# Digital.net
KiCad netlist of a schematic drawn in Altium Designer
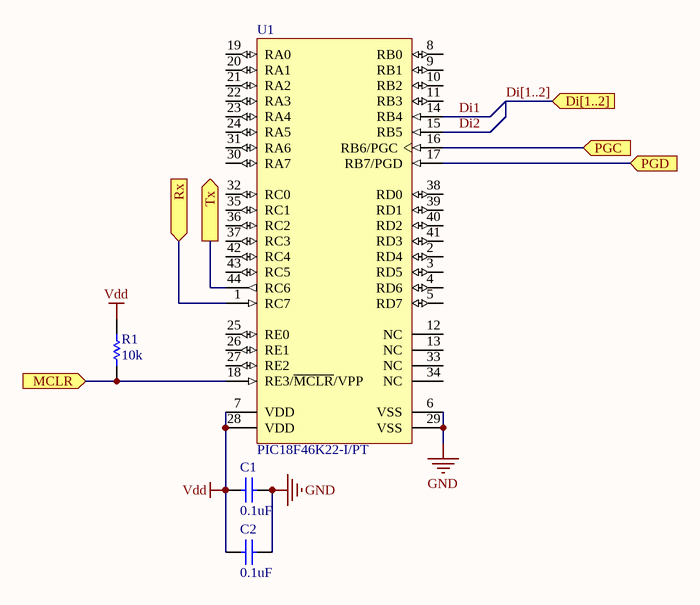
[diagram p0: Digital.SchDoc]

(export (version "E")
  (design (tool "Eeschema 10.0.6"))
  (components
    (comp (ref "C1")
      (value "0.1uF")
      (footprint "1608[0603]")
      (description "Capacitor")
      (fields (field (name "Comment") "Cap") (field (name "PUBLISHER") "Altium Limited"))
      (libsource (lib "Miscellaneous Devices") (part "Cap"))
    )
    (comp (ref "C2")
      (value "0.1uF")
      (footprint "1608[0603]")
      (description "Capacitor")
      (fields (field (name "Comment") "Cap") (field (name "PUBLISHER") "Altium Limited"))
      (libsource (lib "Miscellaneous Devices") (part "Cap"))
    )
    (comp (ref "R1")
      (value "10k")
      (footprint "C1206")
      (description "Resistor")
      (fields (field (name "Comment") "Res1") (field (name "PUBLISHER") "Altium Limited"))
      (libsource (lib "Miscellaneous Devices") (part "Res1"))
    )
    (comp (ref "U1")
      (value "PIC18F46K22-I/PT")
      (footprint "MCHP-TQFP-PT44_N")
      (fields (field (name "MANUFACTURER") "Microchip"))
      (libsource (lib "Microchip PIC18") (part "PIC18F46K22-I/PT"))
    )
  )
  (nets
    (net (code "1") (name "/Di1") (class "Default")
      (node (ref "U1") (pin "14") (pinfunction "RB4_14") (pintype "input"))
    )
    (net (code "2") (name "/Di2") (class "Default")
      (node (ref "U1") (pin "15") (pinfunction "RB5_15") (pintype "input"))
    )
    (net (code "4") (name "/MCLR") (class "Default")
      (node (ref "R1") (pin "2") (pinfunction "2_2") (pintype "passive"))
      (node (ref "U1") (pin "18") (pinfunction "RE3/~{MCLR}/VPP_18") (pintype "input"))
    )
    (net (code "5") (name "/PGC") (class "Default")
      (node (ref "U1") (pin "16") (pinfunction "RB6/PGC_16") (pintype "input"))
    )
    (net (code "6") (name "/PGD") (class "Default")
      (node (ref "U1") (pin "17") (pinfunction "RB7/PGD_17") (pintype "input"))
    )
    (net (code "7") (name "/Rx") (class "Default")
      (node (ref "U1") (pin "1") (pinfunction "RC7_1") (pintype "input"))
    )
    (net (code "8") (name "/Tx") (class "Default")
      (node (ref "U1") (pin "44") (pinfunction "RC6_44") (pintype "output"))
    )
    (net (code "9") (name "GND") (class "Default")
      (node (ref "C1") (pin "1") (pinfunction "1_1") (pintype "passive"))
      (node (ref "C2") (pin "1") (pinfunction "1_1") (pintype "passive"))
      (node (ref "U1") (pin "29") (pinfunction "VSS_29") (pintype "power_in"))
      (node (ref "U1") (pin "6") (pinfunction "VSS_6") (pintype "power_in"))
    )
    (net (code "10") (name "Vdd") (class "Default")
      (node (ref "C1") (pin "2") (pinfunction "2_2") (pintype "passive"))
      (node (ref "C2") (pin "2") (pinfunction "2_2") (pintype "passive"))
      (node (ref "R1") (pin "1") (pinfunction "1_1") (pintype "passive"))
      (node (ref "U1") (pin "28") (pinfunction "VDD_28") (pintype "power_in"))
      (node (ref "U1") (pin "7") (pinfunction "VDD_7") (pintype "power_in"))
    )
    (net (code "11") (name "unconnected-(U1-NC-Pad12)") (class "Default")
      (node (ref "U1") (pin "12") (pinfunction "NC_12") (pintype "passive"))
    )
    (net (code "12") (name "unconnected-(U1-NC-Pad13)") (class "Default")
      (node (ref "U1") (pin "13") (pinfunction "NC_13") (pintype "passive"))
    )
    (net (code "13") (name "unconnected-(U1-NC-Pad33)") (class "Default")
      (node (ref "U1") (pin "33") (pinfunction "NC_33") (pintype "passive"))
    )
    (net (code "14") (name "unconnected-(U1-NC-Pad34)") (class "Default")
      (node (ref "U1") (pin "34") (pinfunction "NC_34") (pintype "passive"))
    )
    (net (code "15") (name "unconnected-(U1-RA0-Pad19)") (class "Default")
      (node (ref "U1") (pin "19") (pinfunction "RA0_19") (pintype "bidirectional"))
    )
    (net (code "16") (name "unconnected-(U1-RA1-Pad20)") (class "Default")
      (node (ref "U1") (pin "20") (pinfunction "RA1_20") (pintype "bidirectional"))
    )
    (net (code "17") (name "unconnected-(U1-RA2-Pad21)") (class "Default")
      (node (ref "U1") (pin "21") (pinfunction "RA2_21") (pintype "bidirectional"))
    )
    (net (code "18") (name "unconnected-(U1-RA3-Pad22)") (class "Default")
      (node (ref "U1") (pin "22") (pinfunction "RA3_22") (pintype "bidirectional"))
    )
    (net (code "19") (name "unconnected-(U1-RA4-Pad23)") (class "Default")
      (node (ref "U1") (pin "23") (pinfunction "RA4_23") (pintype "bidirectional"))
    )
    (net (code "20") (name "unconnected-(U1-RA5-Pad24)") (class "Default")
      (node (ref "U1") (pin "24") (pinfunction "RA5_24") (pintype "bidirectional"))
    )
    (net (code "21") (name "unconnected-(U1-RA6-Pad31)") (class "Default")
      (node (ref "U1") (pin "31") (pinfunction "RA6_31") (pintype "bidirectional"))
    )
    (net (code "22") (name "unconnected-(U1-RA7-Pad30)") (class "Default")
      (node (ref "U1") (pin "30") (pinfunction "RA7_30") (pintype "bidirectional"))
    )
    (net (code "23") (name "unconnected-(U1-RB0-Pad8)") (class "Default")
      (node (ref "U1") (pin "8") (pinfunction "RB0_8") (pintype "bidirectional"))
    )
    (net (code "24") (name "unconnected-(U1-RB1-Pad9)") (class "Default")
      (node (ref "U1") (pin "9") (pinfunction "RB1_9") (pintype "bidirectional"))
    )
    (net (code "25") (name "unconnected-(U1-RB2-Pad10)") (class "Default")
      (node (ref "U1") (pin "10") (pinfunction "RB2_10") (pintype "bidirectional"))
    )
    (net (code "26") (name "unconnected-(U1-RB3-Pad11)") (class "Default")
      (node (ref "U1") (pin "11") (pinfunction "RB3_11") (pintype "bidirectional"))
    )
    (net (code "27") (name "unconnected-(U1-RC0-Pad32)") (class "Default")
      (node (ref "U1") (pin "32") (pinfunction "RC0_32") (pintype "bidirectional"))
    )
    (net (code "28") (name "unconnected-(U1-RC1-Pad35)") (class "Default")
      (node (ref "U1") (pin "35") (pinfunction "RC1_35") (pintype "bidirectional"))
    )
    (net (code "29") (name "unconnected-(U1-RC2-Pad36)") (class "Default")
      (node (ref "U1") (pin "36") (pinfunction "RC2_36") (pintype "bidirectional"))
    )
    (net (code "30") (name "unconnected-(U1-RC3-Pad37)") (class "Default")
      (node (ref "U1") (pin "37") (pinfunction "RC3_37") (pintype "bidirectional"))
    )
    (net (code "31") (name "unconnected-(U1-RC4-Pad42)") (class "Default")
      (node (ref "U1") (pin "42") (pinfunction "RC4_42") (pintype "bidirectional"))
    )
    (net (code "32") (name "unconnected-(U1-RC5-Pad43)") (class "Default")
      (node (ref "U1") (pin "43") (pinfunction "RC5_43") (pintype "bidirectional"))
    )
    (net (code "33") (name "unconnected-(U1-RD0-Pad38)") (class "Default")
      (node (ref "U1") (pin "38") (pinfunction "RD0_38") (pintype "bidirectional"))
    )
    (net (code "34") (name "unconnected-(U1-RD1-Pad39)") (class "Default")
      (node (ref "U1") (pin "39") (pinfunction "RD1_39") (pintype "bidirectional"))
    )
    (net (code "35") (name "unconnected-(U1-RD2-Pad40)") (class "Default")
      (node (ref "U1") (pin "40") (pinfunction "RD2_40") (pintype "bidirectional"))
    )
    (net (code "36") (name "unconnected-(U1-RD3-Pad41)") (class "Default")
      (node (ref "U1") (pin "41") (pinfunction "RD3_41") (pintype "bidirectional"))
    )
    (net (code "37") (name "unconnected-(U1-RD4-Pad2)") (class "Default")
      (node (ref "U1") (pin "2") (pinfunction "RD4_2") (pintype "bidirectional"))
    )
    (net (code "38") (name "unconnected-(U1-RD5-Pad3)") (class "Default")
      (node (ref "U1") (pin "3") (pinfunction "RD5_3") (pintype "bidirectional"))
    )
    (net (code "39") (name "unconnected-(U1-RD6-Pad4)") (class "Default")
      (node (ref "U1") (pin "4") (pinfunction "RD6_4") (pintype "bidirectional"))
    )
    (net (code "40") (name "unconnected-(U1-RD7-Pad5)") (class "Default")
      (node (ref "U1") (pin "5") (pinfunction "RD7_5") (pintype "bidirectional"))
    )
    (net (code "41") (name "unconnected-(U1-RE0-Pad25)") (class "Default")
      (node (ref "U1") (pin "25") (pinfunction "RE0_25") (pintype "bidirectional"))
    )
    (net (code "42") (name "unconnected-(U1-RE1-Pad26)") (class "Default")
      (node (ref "U1") (pin "26") (pinfunction "RE1_26") (pintype "bidirectional"))
    )
    (net (code "43") (name "unconnected-(U1-RE2-Pad27)") (class "Default")
      (node (ref "U1") (pin "27") (pinfunction "RE2_27") (pintype "bidirectional"))
    )
  )
)
